# 7seg-main.net
KiCad netlist of a schematic drawn in EAGLE
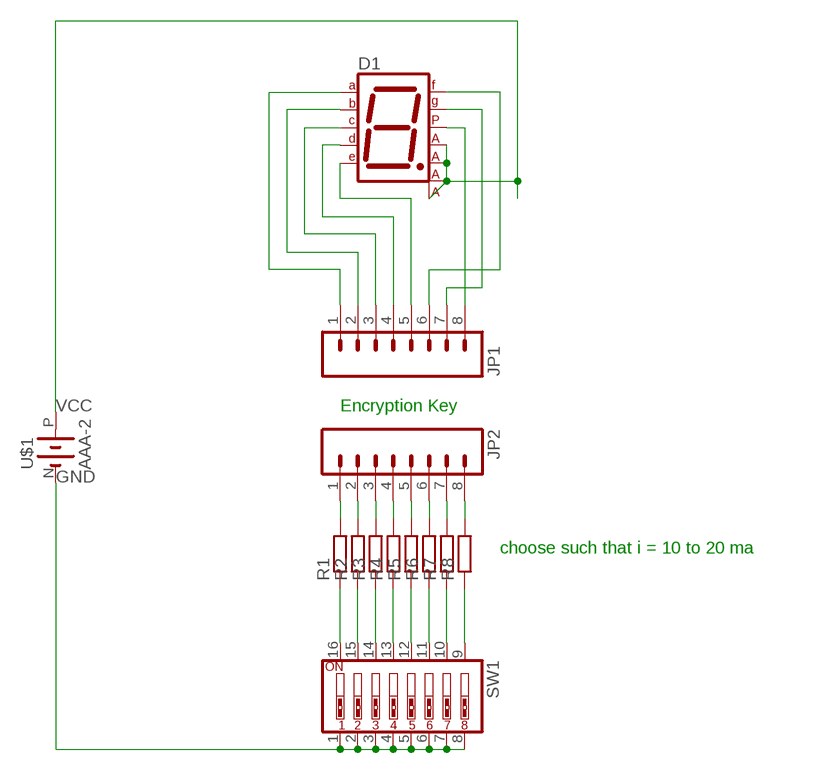
[diagram p0: schematic, sheet 1]

(export (version "E")
  (design (tool "Eeschema 10.0.6"))
  (components
    (comp (ref "D1")
      (value "7SEG-CA-204")
      (footprint "eagle-import:7SEG-0.8IN")
      (libsource (lib "eagle-import") (part "7SEG-CA-204"))
    )
    (comp (ref "JP1")
      (value "M08LOCK_LONGPADS")
      (footprint "eagle-import:1X08_LOCK_LONGPADS")
      (libsource (lib "eagle-import") (part "M08LOCK_LONGPADS"))
    )
    (comp (ref "JP2")
      (value "M08LOCK_LONGPADS")
      (footprint "eagle-import:1X08_LOCK_LONGPADS")
      (libsource (lib "eagle-import") (part "M08LOCK_LONGPADS"))
    )
    (comp (ref "R1")
      (value "RESISTOR_0207/10")
      (footprint "eagle-import:0207_10")
      (libsource (lib "eagle-import") (part "RESISTOR_0207/10"))
    )
    (comp (ref "R2")
      (value "RESISTOR_0207/10")
      (footprint "eagle-import:0207_10")
      (libsource (lib "eagle-import") (part "RESISTOR_0207/10"))
    )
    (comp (ref "R3")
      (value "RESISTOR_0207/10")
      (footprint "eagle-import:0207_10")
      (libsource (lib "eagle-import") (part "RESISTOR_0207/10"))
    )
    (comp (ref "R4")
      (value "RESISTOR_0207/10")
      (footprint "eagle-import:0207_10")
      (libsource (lib "eagle-import") (part "RESISTOR_0207/10"))
    )
    (comp (ref "R5")
      (value "RESISTOR_0207/10")
      (footprint "eagle-import:0207_10")
      (libsource (lib "eagle-import") (part "RESISTOR_0207/10"))
    )
    (comp (ref "R6")
      (value "RESISTOR_0207/10")
      (footprint "eagle-import:0207_10")
      (libsource (lib "eagle-import") (part "RESISTOR_0207/10"))
    )
    (comp (ref "R7")
      (value "RESISTOR_0207/10")
      (footprint "eagle-import:0207_10")
      (libsource (lib "eagle-import") (part "RESISTOR_0207/10"))
    )
    (comp (ref "R8")
      (value "RESISTOR_0207/10")
      (footprint "eagle-import:0207_10")
      (libsource (lib "eagle-import") (part "RESISTOR_0207/10"))
    )
    (comp (ref "SW1")
      (value "SW_DIP-8")
      (footprint "eagle-import:EDG-08")
      (libsource (lib "eagle-import") (part "SW_DIP-8"))
    )
    (comp (ref "U$1")
      (value "AAA-2")
      (footprint "eagle-import:AA-2")
      (libsource (lib "eagle-import") (part "AAA-2"))
    )
  )
  (nets
    (net (code "1") (name "/GND") (class "Default")
      (node (ref "SW1") (pin "1") (pinfunction "1_1") (pintype "passive"))
      (node (ref "SW1") (pin "2") (pinfunction "2_2") (pintype "passive"))
      (node (ref "SW1") (pin "3") (pinfunction "3_3") (pintype "passive"))
      (node (ref "SW1") (pin "4") (pinfunction "4_4") (pintype "passive"))
      (node (ref "SW1") (pin "5") (pinfunction "5_5") (pintype "passive"))
      (node (ref "SW1") (pin "6") (pinfunction "6_6") (pintype "passive"))
      (node (ref "SW1") (pin "7") (pinfunction "7_7") (pintype "passive"))
      (node (ref "SW1") (pin "8") (pinfunction "8_8") (pintype "passive"))
      (node (ref "U$1") (pin "N") (pinfunction "-_N") (pintype "passive"))
    )
    (net (code "2") (name "/VCC") (class "Default")
      (node (ref "D1") (pin "11") (pinfunction "CA3_11") (pintype "passive"))
      (node (ref "D1") (pin "16") (pinfunction "CA4_16") (pintype "passive"))
      (node (ref "D1") (pin "3") (pinfunction "CA1_3") (pintype "passive"))
      (node (ref "D1") (pin "5") (pinfunction "CA2_5") (pintype "passive"))
      (node (ref "U$1") (pin "P") (pinfunction "+_P") (pintype "passive"))
    )
    (net (code "3") (name "Net-(D1-A)") (class "Default")
      (node (ref "D1") (pin "1") (pinfunction "A_1") (pintype "passive"))
      (node (ref "JP1") (pin "1") (pinfunction "1_1") (pintype "passive"))
    )
    (net (code "4") (name "Net-(D1-B)") (class "Default")
      (node (ref "D1") (pin "14") (pinfunction "B_14") (pintype "passive"))
      (node (ref "JP1") (pin "2") (pinfunction "2_2") (pintype "passive"))
    )
    (net (code "5") (name "Net-(D1-C)") (class "Default")
      (node (ref "D1") (pin "12") (pinfunction "C_12") (pintype "passive"))
      (node (ref "JP1") (pin "3") (pinfunction "3_3") (pintype "passive"))
    )
    (net (code "6") (name "Net-(D1-D)") (class "Default")
      (node (ref "D1") (pin "10") (pinfunction "D_10") (pintype "passive"))
      (node (ref "JP1") (pin "4") (pinfunction "4_4") (pintype "passive"))
    )
    (net (code "7") (name "Net-(D1-DP)") (class "Default")
      (node (ref "D1") (pin "9") (pinfunction "DP_9") (pintype "passive"))
      (node (ref "JP1") (pin "8") (pinfunction "8_8") (pintype "passive"))
    )
    (net (code "8") (name "Net-(D1-E)") (class "Default")
      (node (ref "D1") (pin "4") (pinfunction "E_4") (pintype "passive"))
      (node (ref "JP1") (pin "5") (pinfunction "5_5") (pintype "passive"))
    )
    (net (code "9") (name "Net-(D1-F)") (class "Default")
      (node (ref "D1") (pin "2") (pinfunction "F_2") (pintype "passive"))
      (node (ref "JP1") (pin "6") (pinfunction "6_6") (pintype "passive"))
    )
    (net (code "10") (name "Net-(D1-G)") (class "Default")
      (node (ref "D1") (pin "13") (pinfunction "G_13") (pintype "passive"))
      (node (ref "JP1") (pin "7") (pinfunction "7_7") (pintype "passive"))
    )
    (net (code "11") (name "Net-(JP2-Pad1)") (class "Default")
      (node (ref "JP2") (pin "1") (pinfunction "1_1") (pintype "passive"))
      (node (ref "R1") (pin "2") (pinfunction "2_2") (pintype "passive"))
    )
    (net (code "12") (name "Net-(JP2-Pad2)") (class "Default")
      (node (ref "JP2") (pin "2") (pinfunction "2_2") (pintype "passive"))
      (node (ref "R2") (pin "2") (pinfunction "2_2") (pintype "passive"))
    )
    (net (code "13") (name "Net-(JP2-Pad3)") (class "Default")
      (node (ref "JP2") (pin "3") (pinfunction "3_3") (pintype "passive"))
      (node (ref "R3") (pin "2") (pinfunction "2_2") (pintype "passive"))
    )
    (net (code "14") (name "Net-(JP2-Pad4)") (class "Default")
      (node (ref "JP2") (pin "4") (pinfunction "4_4") (pintype "passive"))
      (node (ref "R4") (pin "2") (pinfunction "2_2") (pintype "passive"))
    )
    (net (code "15") (name "Net-(JP2-Pad5)") (class "Default")
      (node (ref "JP2") (pin "5") (pinfunction "5_5") (pintype "passive"))
      (node (ref "R5") (pin "2") (pinfunction "2_2") (pintype "passive"))
    )
    (net (code "16") (name "Net-(JP2-Pad6)") (class "Default")
      (node (ref "JP2") (pin "6") (pinfunction "6_6") (pintype "passive"))
      (node (ref "R6") (pin "2") (pinfunction "2_2") (pintype "passive"))
    )
    (net (code "17") (name "Net-(JP2-Pad7)") (class "Default")
      (node (ref "JP2") (pin "7") (pinfunction "7_7") (pintype "passive"))
      (node (ref "R7") (pin "2") (pinfunction "2_2") (pintype "passive"))
    )
    (net (code "18") (name "Net-(JP2-Pad8)") (class "Default")
      (node (ref "JP2") (pin "8") (pinfunction "8_8") (pintype "passive"))
      (node (ref "R8") (pin "2") (pinfunction "2_2") (pintype "passive"))
    )
    (net (code "19") (name "Net-(R1-Pad1)") (class "Default")
      (node (ref "R1") (pin "1") (pinfunction "1_1") (pintype "passive"))
      (node (ref "SW1") (pin "16") (pinfunction "16_16") (pintype "passive"))
    )
    (net (code "20") (name "Net-(R2-Pad1)") (class "Default")
      (node (ref "R2") (pin "1") (pinfunction "1_1") (pintype "passive"))
      (node (ref "SW1") (pin "15") (pinfunction "15_15") (pintype "passive"))
    )
    (net (code "21") (name "Net-(R3-Pad1)") (class "Default")
      (node (ref "R3") (pin "1") (pinfunction "1_1") (pintype "passive"))
      (node (ref "SW1") (pin "14") (pinfunction "14_14") (pintype "passive"))
    )
    (net (code "22") (name "Net-(R4-Pad1)") (class "Default")
      (node (ref "R4") (pin "1") (pinfunction "1_1") (pintype "passive"))
      (node (ref "SW1") (pin "13") (pinfunction "13_13") (pintype "passive"))
    )
    (net (code "23") (name "Net-(R5-Pad1)") (class "Default")
      (node (ref "R5") (pin "1") (pinfunction "1_1") (pintype "passive"))
      (node (ref "SW1") (pin "12") (pinfunction "12_12") (pintype "passive"))
    )
    (net (code "24") (name "Net-(R6-Pad1)") (class "Default")
      (node (ref "R6") (pin "1") (pinfunction "1_1") (pintype "passive"))
      (node (ref "SW1") (pin "11") (pinfunction "11_11") (pintype "passive"))
    )
    (net (code "25") (name "Net-(R7-Pad1)") (class "Default")
      (node (ref "R7") (pin "1") (pinfunction "1_1") (pintype "passive"))
      (node (ref "SW1") (pin "10") (pinfunction "10_10") (pintype "passive"))
    )
    (net (code "26") (name "Net-(R8-Pad1)") (class "Default")
      (node (ref "R8") (pin "1") (pinfunction "1_1") (pintype "passive"))
      (node (ref "SW1") (pin "9") (pinfunction "9_9") (pintype "passive"))
    )
  )
)
